# AcceleratedLED.net
KiCad netlist of a schematic drawn in EAGLE
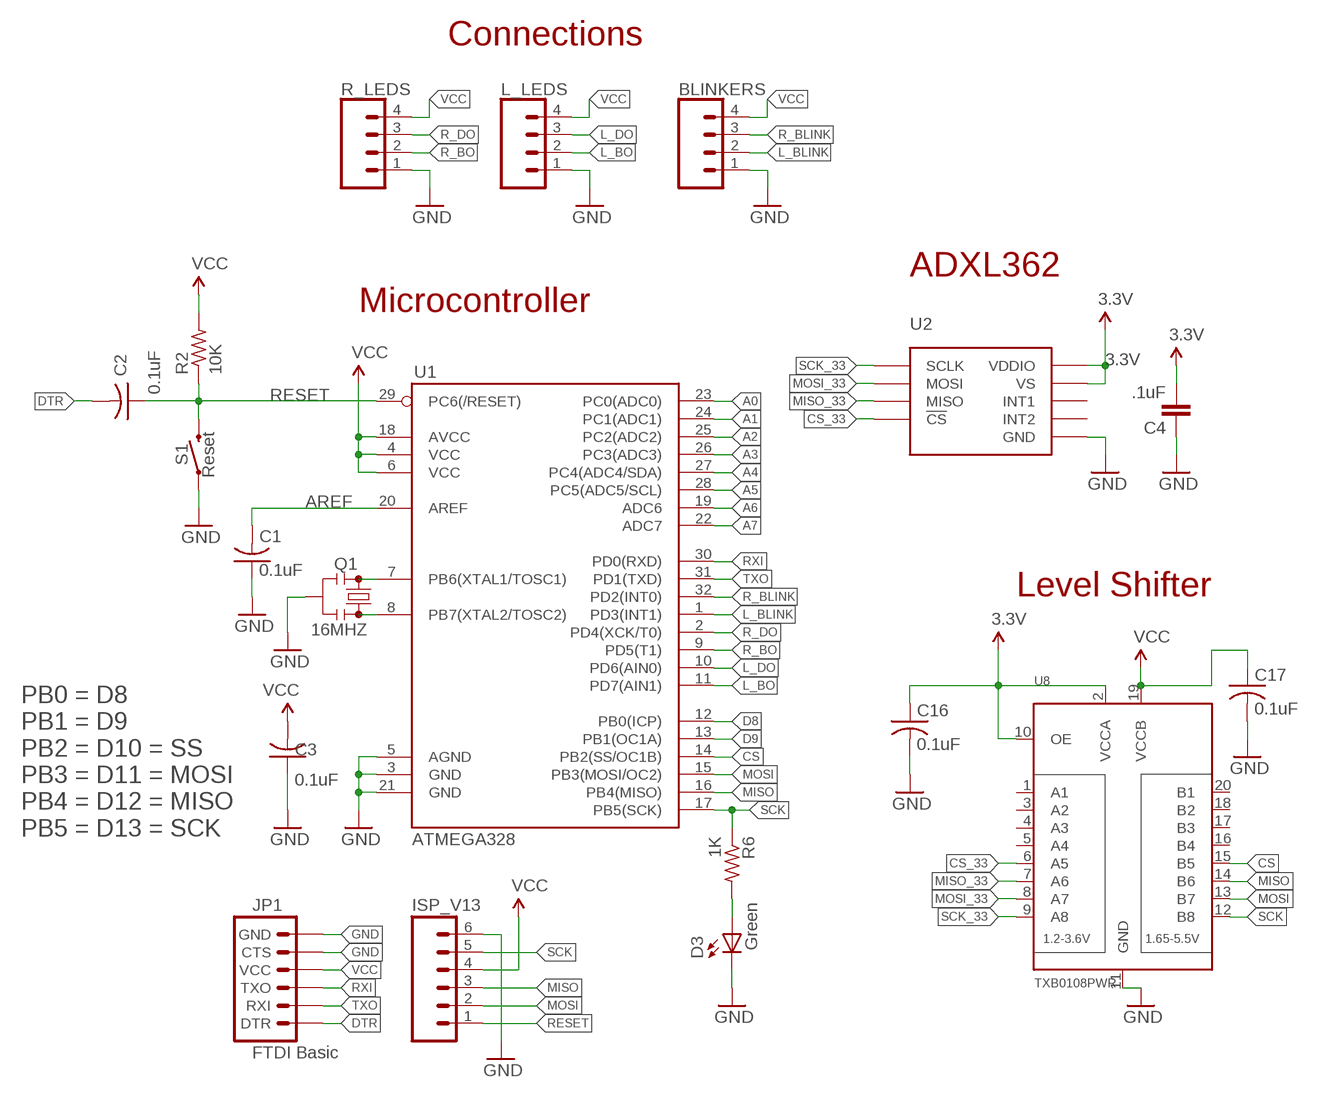
[diagram p0: schematic, sheet 1]

(export (version "E")
  (design (tool "Eeschema 10.0.6"))
  (components
    (comp (ref "BLINKERS")
      (value "CONN_04JST-PTH")
      (footprint "eagle-import:JST-4-PTH")
      (libsource (lib "eagle-import") (part "CONN_04JST-PTH"))
    )
    (comp (ref "C1")
      (value "0.1uF")
      (footprint "eagle-import:C0805")
      (libsource (lib "eagle-import") (part "C-USC0805"))
    )
    (comp (ref "C2")
      (value "0.1uF")
      (footprint "eagle-import:C0805")
      (libsource (lib "eagle-import") (part "C-USC0805"))
    )
    (comp (ref "C3")
      (value "0.1uF")
      (footprint "eagle-import:C0805")
      (libsource (lib "eagle-import") (part "C-USC0805"))
    )
    (comp (ref "C4")
      (value ".1uF")
      (footprint "eagle-import:0603-CAP")
      (fields (field (name "PROD_ID") "CAP-00810"))
      (libsource (lib "eagle-import") (part "0.1UF-25V(+80/-20%)(0603)"))
    )
    (comp (ref "C16")
      (value "0.1uF")
      (footprint "eagle-import:C0805")
      (libsource (lib "eagle-import") (part "rcl_334_C-USC0805"))
    )
    (comp (ref "C17")
      (value "0.1uF")
      (footprint "eagle-import:C0805")
      (libsource (lib "eagle-import") (part "rcl_334_C-USC0805"))
    )
    (comp (ref "D3")
      (value "Green")
      (footprint "eagle-import:CHIPLED_0805")
      (libsource (lib "eagle-import") (part "LEDCHIPLED_0805"))
    )
    (comp (ref "ISP_V13")
      (value "M06SIP")
      (footprint "eagle-import:1X06")
      (libsource (lib "eagle-import") (part "M06SIP"))
    )
    (comp (ref "JP1")
      (value "FTDI Basic")
      (footprint "eagle-import:1X06")
      (libsource (lib "eagle-import") (part "ARDUINO_SERIAL_PROGRAMPTH"))
    )
    (comp (ref "L_LEDS")
      (value "CONN_04JST-PTH")
      (footprint "eagle-import:JST-4-PTH")
      (libsource (lib "eagle-import") (part "CONN_04JST-PTH"))
    )
    (comp (ref "Q1")
      (value "16MHZ")
      (footprint "eagle-import:RESONATOR-SMD")
      (libsource (lib "eagle-import") (part "RESONATOR16MHZ"))
    )
    (comp (ref "R2")
      (value "10K")
      (footprint "eagle-import:M0805")
      (libsource (lib "eagle-import") (part "R-US_M0805"))
    )
    (comp (ref "R6")
      (value "1K")
      (footprint "eagle-import:M0805")
      (libsource (lib "eagle-import") (part "R-US_M0805"))
    )
    (comp (ref "R_LEDS")
      (value "CONN_04JST-PTH")
      (footprint "eagle-import:JST-4-PTH")
      (libsource (lib "eagle-import") (part "CONN_04JST-PTH"))
    )
    (comp (ref "S1")
      (value "Reset")
      (footprint "eagle-import:TACTILE_SWITCH_SMD_5.2MM")
      (libsource (lib "eagle-import") (part "MOMENTARY-SWITCH-SPST-SMD-5.2-REDUNDANT"))
    )
    (comp (ref "U1")
      (value "ATMEGA328")
      (footprint "eagle-import:TQFP32-08")
      (libsource (lib "eagle-import") (part "ATMEGA168"))
    )
    (comp (ref "U2")
      (value "ADXL362ADXL362-1:1")
      (footprint "eagle-import:ADXL362-1_1")
      (libsource (lib "eagle-import") (part "ADXL362ADXL362-1{colon}1"))
    )
    (comp (ref "U8")
      (value "TXB0108PWR")
      (footprint "eagle-import:TSSOP20")
      (libsource (lib "eagle-import") (part "TXB0108PWR"))
    )
  )
  (nets
    (net (code "1") (name "/AREF") (class "Default")
      (node (ref "C1") (pin "2") (pinfunction "2_2") (pintype "passive"))
      (node (ref "U1") (pin "20") (pinfunction "AREF_20") (pintype "bidirectional"))
    )
    (net (code "2") (name "3.3V") (class "Default")
      (node (ref "C16") (pin "1") (pinfunction "1_1") (pintype "passive"))
      (node (ref "C4") (pin "2") (pinfunction "2_2") (pintype "passive"))
      (node (ref "U2") (pin "P$1") (pinfunction "VDDIO_P$1") (pintype "bidirectional"))
      (node (ref "U2") (pin "P$14") (pinfunction "VS_P$14") (pintype "bidirectional"))
      (node (ref "U8") (pin "10") (pinfunction "OE_10") (pintype "bidirectional"))
      (node (ref "U8") (pin "2") (pinfunction "VCCA_2") (pintype "bidirectional"))
    )
    (net (code "3") (name "A0") (class "Default")
      (node (ref "U1") (pin "23") (pinfunction "PC0(ADC0)_23") (pintype "bidirectional"))
    )
    (net (code "4") (name "A1") (class "Default")
      (node (ref "U1") (pin "24") (pinfunction "PC1(ADC1)_24") (pintype "bidirectional"))
    )
    (net (code "5") (name "A2") (class "Default")
      (node (ref "U1") (pin "25") (pinfunction "PC2(ADC2)_25") (pintype "bidirectional"))
    )
    (net (code "6") (name "A3") (class "Default")
      (node (ref "U1") (pin "26") (pinfunction "PC3(ADC3)_26") (pintype "bidirectional"))
    )
    (net (code "7") (name "A4") (class "Default")
      (node (ref "U1") (pin "27") (pinfunction "PC4(ADC4/SDA)_27") (pintype "bidirectional"))
    )
    (net (code "8") (name "A5") (class "Default")
      (node (ref "U1") (pin "28") (pinfunction "PC5(ADC5/SCL)_28") (pintype "bidirectional"))
    )
    (net (code "9") (name "A6") (class "Default")
      (node (ref "U1") (pin "19") (pinfunction "ADC6_19") (pintype "bidirectional"))
    )
    (net (code "10") (name "A7") (class "Default")
      (node (ref "U1") (pin "22") (pinfunction "ADC7_22") (pintype "bidirectional"))
    )
    (net (code "11") (name "CS") (class "Default")
      (node (ref "U1") (pin "14") (pinfunction "PB2(SS/OC1B)_14") (pintype "bidirectional"))
      (node (ref "U8") (pin "15") (pinfunction "B5_15") (pintype "bidirectional"))
    )
    (net (code "12") (name "CS_33") (class "Default")
      (node (ref "U2") (pin "P$8") (pinfunction "~{CS}_P$8") (pintype "bidirectional"))
      (node (ref "U8") (pin "6") (pinfunction "A5_6") (pintype "bidirectional"))
    )
    (net (code "13") (name "D8") (class "Default")
      (node (ref "U1") (pin "12") (pinfunction "PB0(ICP)_12") (pintype "bidirectional"))
    )
    (net (code "14") (name "D9") (class "Default")
      (node (ref "U1") (pin "13") (pinfunction "PB1(OC1A)_13") (pintype "bidirectional"))
    )
    (net (code "15") (name "DTR") (class "Default")
      (node (ref "C2") (pin "2") (pinfunction "2_2") (pintype "passive"))
      (node (ref "JP1") (pin "1") (pinfunction "DTR_1") (pintype "passive"))
    )
    (net (code "16") (name "GND") (class "Default")
      (node (ref "BLINKERS") (pin "1") (pinfunction "1_1") (pintype "passive"))
      (node (ref "C1") (pin "1") (pinfunction "1_1") (pintype "passive"))
      (node (ref "C16") (pin "2") (pinfunction "2_2") (pintype "passive"))
      (node (ref "C17") (pin "2") (pinfunction "2_2") (pintype "passive"))
      (node (ref "C3") (pin "1") (pinfunction "1_1") (pintype "passive"))
      (node (ref "C4") (pin "1") (pinfunction "1_1") (pintype "passive"))
      (node (ref "D3") (pin "C") (pinfunction "C_C") (pintype "passive"))
      (node (ref "ISP_V13") (pin "6") (pinfunction "6_6") (pintype "passive"))
      (node (ref "JP1") (pin "5") (pinfunction "CTS_5") (pintype "passive"))
      (node (ref "JP1") (pin "6") (pinfunction "GND_6") (pintype "passive"))
      (node (ref "L_LEDS") (pin "1") (pinfunction "1_1") (pintype "passive"))
      (node (ref "Q1") (pin "2") (pinfunction "2_2") (pintype "passive"))
      (node (ref "R_LEDS") (pin "1") (pinfunction "1_1") (pintype "passive"))
      (node (ref "S1") (pin "1") (pinfunction "1_1") (pintype "passive"))
      (node (ref "S1") (pin "2") (pinfunction "1_2") (pintype "passive"))
      (node (ref "U1") (pin "21") (pinfunction "GND_21") (pintype "bidirectional"))
      (node (ref "U1") (pin "3") (pinfunction "GND_3") (pintype "bidirectional"))
      (node (ref "U1") (pin "5") (pinfunction "AGND_5") (pintype "bidirectional"))
      (node (ref "U2") (pin "P$12") (pinfunction "GND_P$12") (pintype "bidirectional"))
      (node (ref "U2") (pin "P$13") (pinfunction "GND_P$13") (pintype "bidirectional"))
      (node (ref "U2") (pin "P$16") (pinfunction "GND_P$16") (pintype "bidirectional"))
      (node (ref "U8") (pin "11") (pinfunction "GND_11") (pintype "bidirectional"))
    )
    (net (code "17") (name "L_BLINK") (class "Default")
      (node (ref "BLINKERS") (pin "2") (pinfunction "2_2") (pintype "passive"))
      (node (ref "U1") (pin "1") (pinfunction "PD3(INT1)_1") (pintype "bidirectional"))
    )
    (net (code "18") (name "L_BO") (class "Default")
      (node (ref "L_LEDS") (pin "2") (pinfunction "2_2") (pintype "passive"))
      (node (ref "U1") (pin "11") (pinfunction "PD7(AIN1)_11") (pintype "bidirectional"))
    )
    (net (code "19") (name "L_DO") (class "Default")
      (node (ref "L_LEDS") (pin "3") (pinfunction "3_3") (pintype "passive"))
      (node (ref "U1") (pin "10") (pinfunction "PD6(AIN0)_10") (pintype "bidirectional"))
    )
    (net (code "20") (name "MISO") (class "Default")
      (node (ref "ISP_V13") (pin "3") (pinfunction "3_3") (pintype "passive"))
      (node (ref "U1") (pin "16") (pinfunction "PB4(MISO)_16") (pintype "bidirectional"))
      (node (ref "U8") (pin "14") (pinfunction "B6_14") (pintype "bidirectional"))
    )
    (net (code "21") (name "MISO_33") (class "Default")
      (node (ref "U2") (pin "P$7") (pinfunction "MISO_P$7") (pintype "bidirectional"))
      (node (ref "U8") (pin "7") (pinfunction "A6_7") (pintype "bidirectional"))
    )
    (net (code "22") (name "MOSI") (class "Default")
      (node (ref "ISP_V13") (pin "2") (pinfunction "2_2") (pintype "passive"))
      (node (ref "U1") (pin "15") (pinfunction "PB3(MOSI/OC2)_15") (pintype "bidirectional"))
      (node (ref "U8") (pin "13") (pinfunction "B7_13") (pintype "bidirectional"))
    )
    (net (code "23") (name "MOSI_33") (class "Default")
      (node (ref "U2") (pin "P$6") (pinfunction "MOSI_P$6") (pintype "bidirectional"))
      (node (ref "U8") (pin "8") (pinfunction "A7_8") (pintype "bidirectional"))
    )
    (net (code "24") (name "Net-(D3-PadA)") (class "Default")
      (node (ref "D3") (pin "A") (pinfunction "A_A") (pintype "passive"))
      (node (ref "R6") (pin "2") (pinfunction "2_2") (pintype "passive"))
    )
    (net (code "25") (name "Net-(U1-PB6(XTAL1{slash}TOSC1))") (class "Default")
      (node (ref "Q1") (pin "1") (pinfunction "1_1") (pintype "passive"))
      (node (ref "U1") (pin "7") (pinfunction "PB6(XTAL1/TOSC1)_7") (pintype "bidirectional"))
    )
    (net (code "26") (name "Net-(U1-PB7(XTAL2{slash}TOSC2))") (class "Default")
      (node (ref "Q1") (pin "3") (pinfunction "3_3") (pintype "passive"))
      (node (ref "U1") (pin "8") (pinfunction "PB7(XTAL2/TOSC2)_8") (pintype "bidirectional"))
    )
    (net (code "27") (name "RESET") (class "Default")
      (node (ref "C2") (pin "1") (pinfunction "1_1") (pintype "passive"))
      (node (ref "ISP_V13") (pin "1") (pinfunction "1_1") (pintype "passive"))
      (node (ref "R2") (pin "1") (pinfunction "1_1") (pintype "passive"))
      (node (ref "S1") (pin "3") (pinfunction "2_3") (pintype "passive"))
      (node (ref "S1") (pin "4") (pinfunction "2_4") (pintype "passive"))
      (node (ref "U1") (pin "29") (pinfunction "PC6(/RESET)_29") (pintype "bidirectional"))
    )
    (net (code "28") (name "RXI") (class "Default")
      (node (ref "JP1") (pin "3") (pinfunction "TXO_3") (pintype "passive"))
      (node (ref "U1") (pin "30") (pinfunction "PD0(RXD)_30") (pintype "bidirectional"))
    )
    (net (code "29") (name "R_BLINK") (class "Default")
      (node (ref "BLINKERS") (pin "3") (pinfunction "3_3") (pintype "passive"))
      (node (ref "U1") (pin "32") (pinfunction "PD2(INT0)_32") (pintype "bidirectional"))
    )
    (net (code "30") (name "R_BO") (class "Default")
      (node (ref "R_LEDS") (pin "2") (pinfunction "2_2") (pintype "passive"))
      (node (ref "U1") (pin "9") (pinfunction "PD5(T1)_9") (pintype "bidirectional"))
    )
    (net (code "31") (name "R_DO") (class "Default")
      (node (ref "R_LEDS") (pin "3") (pinfunction "3_3") (pintype "passive"))
      (node (ref "U1") (pin "2") (pinfunction "PD4(XCK/T0)_2") (pintype "bidirectional"))
    )
    (net (code "32") (name "SCK") (class "Default")
      (node (ref "ISP_V13") (pin "5") (pinfunction "5_5") (pintype "passive"))
      (node (ref "R6") (pin "1") (pinfunction "1_1") (pintype "passive"))
      (node (ref "U1") (pin "17") (pinfunction "PB5(SCK)_17") (pintype "bidirectional"))
      (node (ref "U8") (pin "12") (pinfunction "B8_12") (pintype "bidirectional"))
    )
    (net (code "33") (name "SCK_33") (class "Default")
      (node (ref "U2") (pin "P$4") (pinfunction "SCLK_P$4") (pintype "bidirectional"))
      (node (ref "U8") (pin "9") (pinfunction "A8_9") (pintype "bidirectional"))
    )
    (net (code "34") (name "TXO") (class "Default")
      (node (ref "JP1") (pin "2") (pinfunction "RXI_2") (pintype "passive"))
      (node (ref "U1") (pin "31") (pinfunction "PD1(TXD)_31") (pintype "bidirectional"))
    )
    (net (code "35") (name "VCC") (class "Default")
      (node (ref "BLINKERS") (pin "4") (pinfunction "4_4") (pintype "passive"))
      (node (ref "C17") (pin "1") (pinfunction "1_1") (pintype "passive"))
      (node (ref "C3") (pin "2") (pinfunction "2_2") (pintype "passive"))
      (node (ref "ISP_V13") (pin "4") (pinfunction "4_4") (pintype "passive"))
      (node (ref "JP1") (pin "4") (pinfunction "VCC_4") (pintype "passive"))
      (node (ref "L_LEDS") (pin "4") (pinfunction "4_4") (pintype "passive"))
      (node (ref "R2") (pin "2") (pinfunction "2_2") (pintype "passive"))
      (node (ref "R_LEDS") (pin "4") (pinfunction "4_4") (pintype "passive"))
      (node (ref "U1") (pin "18") (pinfunction "AVCC_18") (pintype "bidirectional"))
      (node (ref "U1") (pin "4") (pinfunction "VCC_4") (pintype "bidirectional"))
      (node (ref "U1") (pin "6") (pinfunction "VCC_6") (pintype "bidirectional"))
      (node (ref "U8") (pin "19") (pinfunction "VCCB_19") (pintype "bidirectional"))
    )
    (net (code "36") (name "unconnected-(U2-INT1-PadP$11)") (class "Default")
      (node (ref "U2") (pin "P$11") (pinfunction "INT1_P$11") (pintype "bidirectional"))
    )
    (net (code "37") (name "unconnected-(U2-INT2-PadP$9)") (class "Default")
      (node (ref "U2") (pin "P$9") (pinfunction "INT2_P$9") (pintype "bidirectional"))
    )
    (net (code "38") (name "unconnected-(U8-A1-Pad1)") (class "Default")
      (node (ref "U8") (pin "1") (pinfunction "A1_1") (pintype "bidirectional"))
    )
    (net (code "39") (name "unconnected-(U8-A2-Pad3)") (class "Default")
      (node (ref "U8") (pin "3") (pinfunction "A2_3") (pintype "bidirectional"))
    )
    (net (code "40") (name "unconnected-(U8-A3-Pad4)") (class "Default")
      (node (ref "U8") (pin "4") (pinfunction "A3_4") (pintype "bidirectional"))
    )
    (net (code "41") (name "unconnected-(U8-A4-Pad5)") (class "Default")
      (node (ref "U8") (pin "5") (pinfunction "A4_5") (pintype "bidirectional"))
    )
    (net (code "42") (name "unconnected-(U8-B1-Pad20)") (class "Default")
      (node (ref "U8") (pin "20") (pinfunction "B1_20") (pintype "bidirectional"))
    )
    (net (code "43") (name "unconnected-(U8-B2-Pad18)") (class "Default")
      (node (ref "U8") (pin "18") (pinfunction "B2_18") (pintype "bidirectional"))
    )
    (net (code "44") (name "unconnected-(U8-B3-Pad17)") (class "Default")
      (node (ref "U8") (pin "17") (pinfunction "B3_17") (pintype "bidirectional"))
    )
    (net (code "45") (name "unconnected-(U8-B4-Pad16)") (class "Default")
      (node (ref "U8") (pin "16") (pinfunction "B4_16") (pintype "bidirectional"))
    )
  )
)
